# FinalSchem.net
KiCad netlist of a schematic drawn in Altium Designer
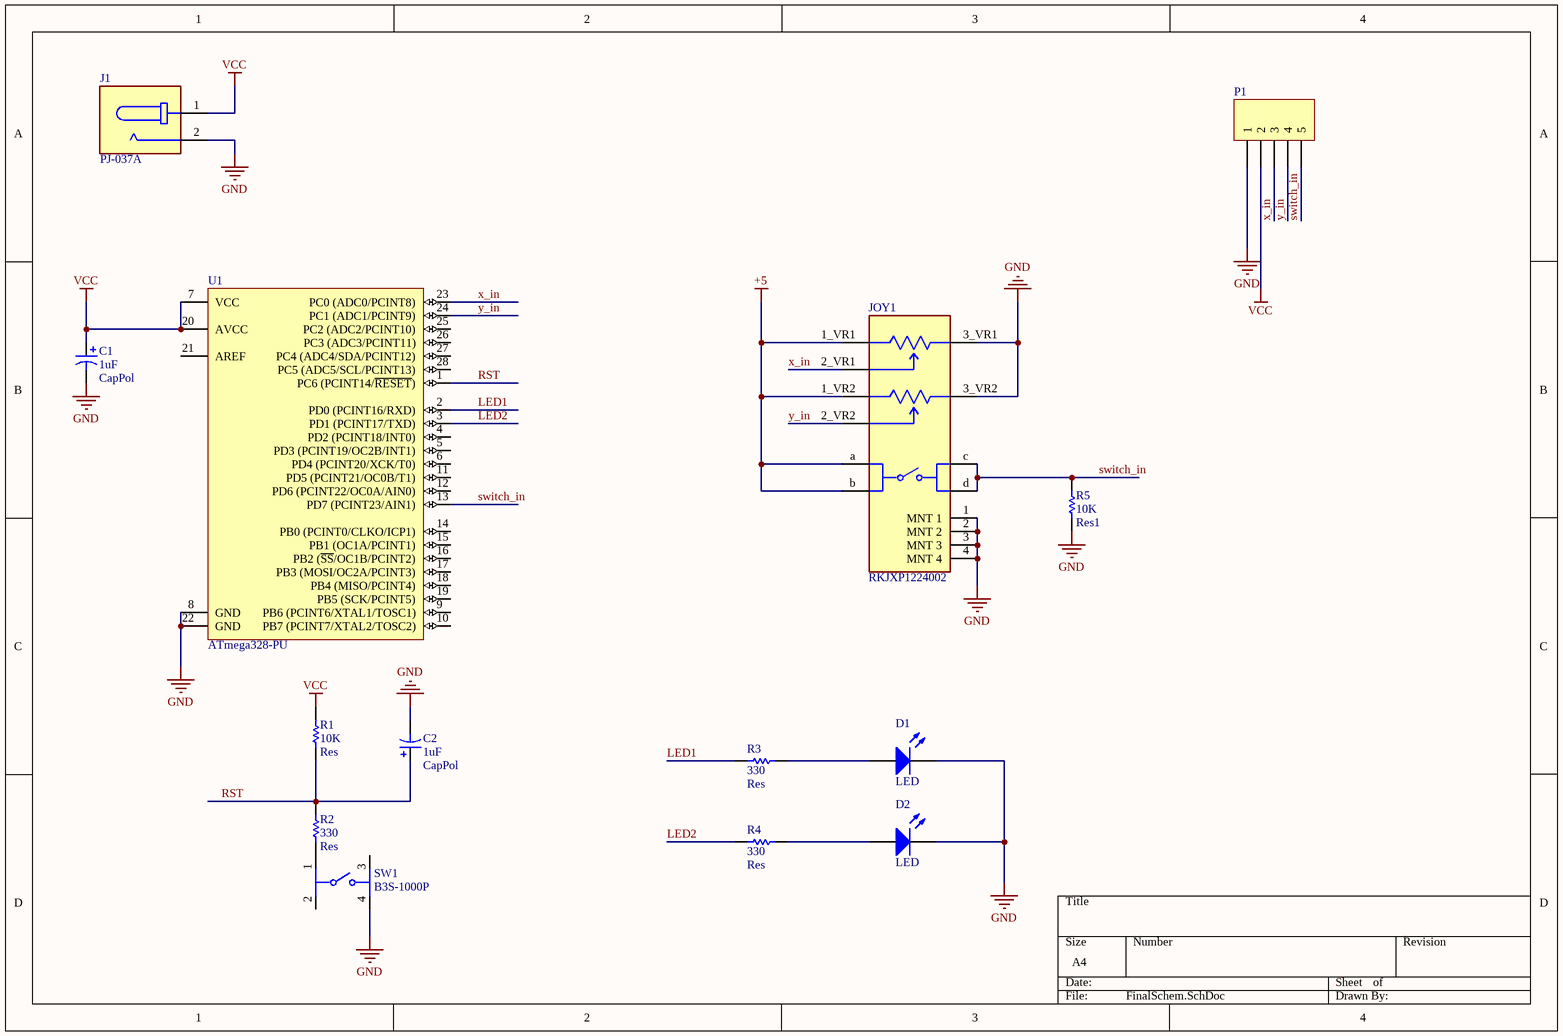
[diagram p0: FinalSchem.SchDoc]

(export (version "E")
  (design (tool "Eeschema 10.0.6"))
  (components
    (comp (ref "C1")
      (value "CapPol")
      (footprint "ElectroCap")
      (description "Polarized Capacitor (Axial)")
      (fields (field (name "ALTIUM_VALUE") "1uF") (field (name "PUBLISHER") "Altium Limited"))
      (libsource (lib "AW25") (part "CapPol"))
    )
    (comp (ref "C2")
      (value "CapPol")
      (footprint "ElectroCap")
      (description "Polarized Capacitor (Axial)")
      (fields (field (name "ALTIUM_VALUE") "1uF") (field (name "PUBLISHER") "Altium Limited"))
      (libsource (lib "AW25") (part "CapPol"))
    )
    (comp (ref "D1")
      (value "LED")
      (footprint "LED")
      (fields (field (name "PUBLISHER") "Altium Limited"))
      (libsource (lib "AW25") (part "LED"))
    )
    (comp (ref "D2")
      (value "LED")
      (footprint "LED")
      (fields (field (name "PUBLISHER") "Altium Limited"))
      (libsource (lib "AW25") (part "LED"))
    )
    (comp (ref "J1")
      (value "PJ-037A")
      (footprint "CUI_PJ-037A")
      (fields (field (name "MF") "{'manufacturer': u'CUI'}"))
      (libsource (lib "AW25") (part "PJ-037A"))
    )
    (comp (ref "JOY1")
      (value "RKJXP1224002")
      (footprint "FP-RKJXP1224002-MFG")
      (description "Multi-Directional Switches LEVER RTRN CNTR PUSH")
      (libsource (lib "Altium Content Vault") (part "b3850d1d0a13d49ba0afb51c7ffb20f"))
    )
    (comp (ref "P1")
      (value "Header 5")
      (footprint "HDR1X5")
      (description "Header, 5-Pin")
      (fields (field (name "PUBLISHER") "Altium Limited"))
      (libsource (lib "AW25") (part "Header 5"))
    )
    (comp (ref "R1")
      (value "Res")
      (footprint "AXIAL-0.4")
      (description "Resistor")
      (fields (field (name "ALTIUM_VALUE") "10K") (field (name "PUBLISHER") "Altium Limited"))
      (libsource (lib "AW25") (part "Res"))
    )
    (comp (ref "R2")
      (value "Res")
      (footprint "AXIAL-0.4")
      (description "Resistor")
      (fields (field (name "ALTIUM_VALUE") "330") (field (name "PUBLISHER") "Altium Limited"))
      (libsource (lib "AW25") (part "Res"))
    )
    (comp (ref "R3")
      (value "Res")
      (footprint "AXIAL-0.4")
      (description "Resistor")
      (fields (field (name "ALTIUM_VALUE") "330") (field (name "PUBLISHER") "Altium Limited"))
      (libsource (lib "AW25") (part "Res"))
    )
    (comp (ref "R4")
      (value "Res")
      (footprint "AXIAL-0.4")
      (description "Resistor")
      (fields (field (name "ALTIUM_VALUE") "330") (field (name "PUBLISHER") "Altium Limited"))
      (libsource (lib "AW25") (part "Res"))
    )
    (comp (ref "R5")
      (value "Res1")
      (footprint "AXIAL-0.3")
      (description "Resistor")
      (fields (field (name "ALTIUM_VALUE") "10K") (field (name "PUBLISHER") "Altium Limited"))
      (libsource (lib "Miscellaneous Devices") (part "Res1"))
    )
    (comp (ref "SW1")
      (value "B3S-1000P")
      (footprint "FP-B3S-1000P-MFG")
      (description "SWITCH TACTILE SPST-NO 0.05A 24V")
      (libsource (lib "AW25") (part "CMP-08834-000008-1"))
    )
    (comp (ref "U1")
      (value "ATmega328-PU")
      (footprint "28P3")
      (libsource (lib "AW25") (part "CMP-0095-00015-2"))
    )
  )
  (nets
    (net (code "1") (name "+5") (class "Default")
      (node (ref "JOY1") (pin "1_VR1") (pinfunction "1_VR1_1_VR1") (pintype "passive"))
      (node (ref "JOY1") (pin "1_VR2") (pinfunction "1_VR2_1_VR2") (pintype "passive"))
      (node (ref "JOY1") (pin "a") (pinfunction "a_a") (pintype "passive"))
      (node (ref "JOY1") (pin "b") (pinfunction "b_b") (pintype "passive"))
    )
    (net (code "2") (name "/LED1") (class "Default")
      (node (ref "R3") (pin "2") (pinfunction "2_2") (pintype "passive"))
      (node (ref "U1") (pin "2") (pinfunction "PD0_(PCINT16/RXD)_2") (pintype "bidirectional"))
    )
    (net (code "3") (name "/LED2") (class "Default")
      (node (ref "R4") (pin "2") (pinfunction "2_2") (pintype "passive"))
      (node (ref "U1") (pin "3") (pinfunction "PD1_(PCINT17/TXD)_3") (pintype "bidirectional"))
    )
    (net (code "4") (name "/RST") (class "Default")
      (node (ref "C2") (pin "1") (pinfunction "1_1") (pintype "passive"))
      (node (ref "R1") (pin "1") (pinfunction "1_1") (pintype "passive"))
      (node (ref "R2") (pin "2") (pinfunction "2_2") (pintype "passive"))
      (node (ref "U1") (pin "1") (pinfunction "PC6_(PCINT14/~{RESET})_1") (pintype "bidirectional"))
    )
    (net (code "5") (name "/switch_in") (class "Default")
      (node (ref "JOY1") (pin "c") (pinfunction "c_c") (pintype "passive"))
      (node (ref "JOY1") (pin "d") (pinfunction "d_d") (pintype "passive"))
      (node (ref "P1") (pin "5") (pinfunction "5_5") (pintype "passive"))
      (node (ref "R5") (pin "2") (pinfunction "2_2") (pintype "passive"))
      (node (ref "U1") (pin "13") (pinfunction "PD7_(PCINT23/AIN1)_13") (pintype "bidirectional"))
    )
    (net (code "6") (name "/x_in") (class "Default")
      (node (ref "JOY1") (pin "2_VR1") (pinfunction "2_VR1_2_VR1") (pintype "passive"))
      (node (ref "P1") (pin "3") (pinfunction "3_3") (pintype "passive"))
      (node (ref "U1") (pin "23") (pinfunction "PC0_(ADC0/PCINT8)_23") (pintype "bidirectional"))
    )
    (net (code "7") (name "/y_in") (class "Default")
      (node (ref "JOY1") (pin "2_VR2") (pinfunction "2_VR2_2_VR2") (pintype "passive"))
      (node (ref "P1") (pin "4") (pinfunction "4_4") (pintype "passive"))
      (node (ref "U1") (pin "24") (pinfunction "PC1_(ADC1/PCINT9)_24") (pintype "bidirectional"))
    )
    (net (code "8") (name "GND") (class "Default")
      (node (ref "C1") (pin "2") (pinfunction "2_2") (pintype "passive"))
      (node (ref "C2") (pin "2") (pinfunction "2_2") (pintype "passive"))
      (node (ref "D1") (pin "2") (pinfunction "K_2") (pintype "passive"))
      (node (ref "D2") (pin "2") (pinfunction "K_2") (pintype "passive"))
      (node (ref "J1") (pin "2") (pinfunction "2_2") (pintype "passive"))
      (node (ref "JOY1") (pin "1") (pinfunction "MNT_1_1") (pintype "passive"))
      (node (ref "JOY1") (pin "2") (pinfunction "MNT_2_2") (pintype "passive"))
      (node (ref "JOY1") (pin "3") (pinfunction "MNT_3_3") (pintype "passive"))
      (node (ref "JOY1") (pin "3_VR1") (pinfunction "3_VR1_3_VR1") (pintype "passive"))
      (node (ref "JOY1") (pin "3_VR2") (pinfunction "3_VR2_3_VR2") (pintype "passive"))
      (node (ref "JOY1") (pin "4") (pinfunction "MNT_4_4") (pintype "passive"))
      (node (ref "P1") (pin "1") (pinfunction "1_1") (pintype "passive"))
      (node (ref "R5") (pin "1") (pinfunction "1_1") (pintype "passive"))
      (node (ref "SW1") (pin "4") (pinfunction "4_4") (pintype "passive"))
      (node (ref "U1") (pin "22") (pinfunction "GND_22") (pintype "power_in"))
      (node (ref "U1") (pin "8") (pinfunction "GND_8") (pintype "power_in"))
    )
    (net (code "9") (name "Net-(D1-A)") (class "Default")
      (node (ref "D1") (pin "1") (pinfunction "A_1") (pintype "passive"))
      (node (ref "R3") (pin "1") (pinfunction "1_1") (pintype "passive"))
    )
    (net (code "10") (name "Net-(D2-A)") (class "Default")
      (node (ref "D2") (pin "1") (pinfunction "A_1") (pintype "passive"))
      (node (ref "R4") (pin "1") (pinfunction "1_1") (pintype "passive"))
    )
    (net (code "11") (name "Net-(R2-Pad1)") (class "Default")
      (node (ref "R2") (pin "1") (pinfunction "1_1") (pintype "passive"))
      (node (ref "SW1") (pin "1") (pinfunction "1_1") (pintype "passive"))
    )
    (net (code "12") (name "VCC") (class "Default")
      (node (ref "C1") (pin "1") (pinfunction "1_1") (pintype "passive"))
      (node (ref "J1") (pin "1") (pinfunction "1_1") (pintype "passive"))
      (node (ref "P1") (pin "2") (pinfunction "2_2") (pintype "passive"))
      (node (ref "R1") (pin "2") (pinfunction "2_2") (pintype "passive"))
      (node (ref "U1") (pin "20") (pinfunction "AVCC_20") (pintype "power_in"))
      (node (ref "U1") (pin "7") (pinfunction "VCC_7") (pintype "power_in"))
    )
    (net (code "13") (name "unconnected-(SW1-Pad2)") (class "Default")
      (node (ref "SW1") (pin "2") (pinfunction "2_2") (pintype "passive"))
    )
    (net (code "14") (name "unconnected-(SW1-Pad3)") (class "Default")
      (node (ref "SW1") (pin "3") (pinfunction "3_3") (pintype "passive"))
    )
    (net (code "15") (name "unconnected-(U1-AREF-Pad21)") (class "Default")
      (node (ref "U1") (pin "21") (pinfunction "AREF_21") (pintype "power_in"))
    )
    (net (code "16") (name "unconnected-(U1-PB0_(PCINT0{slash}CLKO{slash}ICP1)-Pad14)") (class "Default")
      (node (ref "U1") (pin "14") (pinfunction "PB0_(PCINT0/CLKO/ICP1)_14") (pintype "bidirectional"))
    )
    (net (code "17") (name "unconnected-(U1-PB1_(OC1A{slash}PCINT1)-Pad15)") (class "Default")
      (node (ref "U1") (pin "15") (pinfunction "PB1_(OC1A/PCINT1)_15") (pintype "bidirectional"))
    )
    (net (code "18") (name "unconnected-(U1-PB2_(~{SS}{slash}OC1B{slash}PCINT2)-Pad16)") (class "Default")
      (node (ref "U1") (pin "16") (pinfunction "PB2_(~{SS}/OC1B/PCINT2)_16") (pintype "bidirectional"))
    )
    (net (code "19") (name "unconnected-(U1-PB3_(MOSI{slash}OC2A{slash}PCINT3)-Pad17)") (class "Default")
      (node (ref "U1") (pin "17") (pinfunction "PB3_(MOSI/OC2A/PCINT3)_17") (pintype "bidirectional"))
    )
    (net (code "20") (name "unconnected-(U1-PB4_(MISO{slash}PCINT4)-Pad18)") (class "Default")
      (node (ref "U1") (pin "18") (pinfunction "PB4_(MISO/PCINT4)_18") (pintype "bidirectional"))
    )
    (net (code "21") (name "unconnected-(U1-PB5_(SCK{slash}PCINT5)-Pad19)") (class "Default")
      (node (ref "U1") (pin "19") (pinfunction "PB5_(SCK/PCINT5)_19") (pintype "bidirectional"))
    )
    (net (code "22") (name "unconnected-(U1-PB6_(PCINT6{slash}XTAL1{slash}TOSC1)-Pad9)") (class "Default")
      (node (ref "U1") (pin "9") (pinfunction "PB6_(PCINT6/XTAL1/TOSC1)_9") (pintype "bidirectional"))
    )
    (net (code "23") (name "unconnected-(U1-PB7_(PCINT7{slash}XTAL2{slash}TOSC2)-Pad10)") (class "Default")
      (node (ref "U1") (pin "10") (pinfunction "PB7_(PCINT7/XTAL2/TOSC2)_10") (pintype "bidirectional"))
    )
    (net (code "24") (name "unconnected-(U1-PC2_(ADC2{slash}PCINT10)-Pad25)") (class "Default")
      (node (ref "U1") (pin "25") (pinfunction "PC2_(ADC2/PCINT10)_25") (pintype "bidirectional"))
    )
    (net (code "25") (name "unconnected-(U1-PC3_(ADC3{slash}PCINT11)-Pad26)") (class "Default")
      (node (ref "U1") (pin "26") (pinfunction "PC3_(ADC3/PCINT11)_26") (pintype "bidirectional"))
    )
    (net (code "26") (name "unconnected-(U1-PC4_(ADC4{slash}SDA{slash}PCINT12)-Pad27)") (class "Default")
      (node (ref "U1") (pin "27") (pinfunction "PC4_(ADC4/SDA/PCINT12)_27") (pintype "bidirectional"))
    )
    (net (code "27") (name "unconnected-(U1-PC5_(ADC5{slash}SCL{slash}PCINT13)-Pad28)") (class "Default")
      (node (ref "U1") (pin "28") (pinfunction "PC5_(ADC5/SCL/PCINT13)_28") (pintype "bidirectional"))
    )
    (net (code "28") (name "unconnected-(U1-PD2_(PCINT18{slash}INT0)-Pad4)") (class "Default")
      (node (ref "U1") (pin "4") (pinfunction "PD2_(PCINT18/INT0)_4") (pintype "bidirectional"))
    )
    (net (code "29") (name "unconnected-(U1-PD3_(PCINT19{slash}OC2B{slash}INT1)-Pad5)") (class "Default")
      (node (ref "U1") (pin "5") (pinfunction "PD3_(PCINT19/OC2B/INT1)_5") (pintype "bidirectional"))
    )
    (net (code "30") (name "unconnected-(U1-PD4_(PCINT20{slash}XCK{slash}T0)-Pad6)") (class "Default")
      (node (ref "U1") (pin "6") (pinfunction "PD4_(PCINT20/XCK/T0)_6") (pintype "bidirectional"))
    )
    (net (code "31") (name "unconnected-(U1-PD5_(PCINT21{slash}OC0B{slash}T1)-Pad11)") (class "Default")
      (node (ref "U1") (pin "11") (pinfunction "PD5_(PCINT21/OC0B/T1)_11") (pintype "bidirectional"))
    )
    (net (code "32") (name "unconnected-(U1-PD6_(PCINT22{slash}OC0A{slash}AIN0)-Pad12)") (class "Default")
      (node (ref "U1") (pin "12") (pinfunction "PD6_(PCINT22/OC0A/AIN0)_12") (pintype "bidirectional"))
    )
  )
)
